# clock-kit-board-002.net
KiCad netlist of a schematic drawn in EAGLE
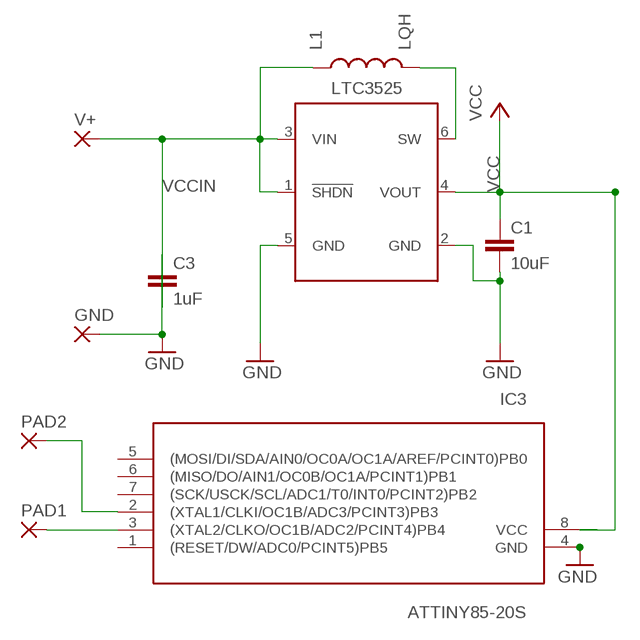
[diagram p0: schematic, sheet 1]

(export (version "E")
  (design (tool "Eeschema 10.0.6"))
  (components
    (comp (ref "C1")
      (value "10uF")
      (footprint "eagle-import:0805")
      (libsource (lib "eagle-import") (part "CAP0805"))
    )
    (comp (ref "C3")
      (value "1uF")
      (footprint "eagle-import:0805")
      (libsource (lib "eagle-import") (part "CAP0805"))
    )
    (comp (ref "GND")
      (value "SMD5")
      (footprint "eagle-import:SMD2,54-5,08")
      (libsource (lib "eagle-import") (part "SMD5"))
    )
    (comp (ref "IC3")
      (value "ATTINY85-20S")
      (footprint "eagle-import:SOIC8")
      (libsource (lib "eagle-import") (part "ATTINY85SV-10"))
    )
    (comp (ref "L1")
      (value "LQH")
      (footprint "eagle-import:LQH32")
      (libsource (lib "eagle-import") (part "LQH"))
    )
    (comp (ref "PAD1")
      (value "1,6/0,9")
      (footprint "eagle-import:1,6_0,9")
      (libsource (lib "eagle-import") (part "1,6/0,9"))
    )
    (comp (ref "PAD2")
      (value "1,6/0,9")
      (footprint "eagle-import:1,6_0,9")
      (libsource (lib "eagle-import") (part "1,6/0,9"))
    )
    (comp (ref "U1")
      (value "LTC3525")
      (footprint "eagle-import:SC70-6L")
      (libsource (lib "eagle-import") (part "LTC3525"))
    )
    (comp (ref "V+")
      (value "SMD5")
      (footprint "eagle-import:SMD2,54-5,08")
      (libsource (lib "eagle-import") (part "SMD5"))
    )
  )
  (nets
    (net (code "1") (name "/VCCIN") (class "Default")
      (node (ref "C3") (pin "2") (pinfunction "2_2") (pintype "passive"))
      (node (ref "L1") (pin "1") (pinfunction "1_1") (pintype "passive"))
      (node (ref "U1") (pin "1") (pinfunction "~{SHDN}_1") (pintype "passive"))
      (node (ref "U1") (pin "3") (pinfunction "VIN_3") (pintype "input"))
      (node (ref "V+") (pin "1") (pinfunction "P_1") (pintype "passive"))
    )
    (net (code "2") (name "GND") (class "Default")
      (node (ref "C1") (pin "2") (pinfunction "2_2") (pintype "passive"))
      (node (ref "C3") (pin "1") (pinfunction "1_1") (pintype "passive"))
      (node (ref "GND") (pin "1") (pinfunction "P_1") (pintype "passive"))
      (node (ref "IC3") (pin "4") (pinfunction "GND_4") (pintype "bidirectional"))
      (node (ref "U1") (pin "2") (pinfunction "GND_2") (pintype "power_in"))
      (node (ref "U1") (pin "5") (pinfunction "GND_5") (pintype "input"))
    )
    (net (code "3") (name "Net-(IC3-(XTAL1{slash}CLKI{slash}OC1B{slash}ADC3{slash}PCINT3)PB3)") (class "Default")
      (node (ref "IC3") (pin "2") (pinfunction "(XTAL1/CLKI/OC1B/ADC3/PCINT3)PB3_2") (pintype "bidirectional"))
      (node (ref "PAD2") (pin "1") (pinfunction "P_1") (pintype "passive"))
    )
    (net (code "4") (name "Net-(IC3-(XTAL2{slash}CLKO{slash}OC1B{slash}ADC2{slash}PCINT4)PB4)") (class "Default")
      (node (ref "IC3") (pin "3") (pinfunction "(XTAL2/CLKO/OC1B/ADC2/PCINT4)PB4_3") (pintype "bidirectional"))
      (node (ref "PAD1") (pin "1") (pinfunction "P_1") (pintype "passive"))
    )
    (net (code "5") (name "Net-(U1-SW)") (class "Default")
      (node (ref "L1") (pin "2") (pinfunction "2_2") (pintype "passive"))
      (node (ref "U1") (pin "6") (pinfunction "SW_6") (pintype "passive"))
    )
    (net (code "6") (name "VCC") (class "Default")
      (node (ref "C1") (pin "1") (pinfunction "1_1") (pintype "passive"))
      (node (ref "IC3") (pin "8") (pinfunction "VCC_8") (pintype "bidirectional"))
      (node (ref "U1") (pin "4") (pinfunction "VOUT_4") (pintype "passive"))
    )
    (net (code "7") (name "unconnected-(IC3-(MISO{slash}DO{slash}AIN1{slash}OC0B{slash}OC1A{slash}PCINT1)PB1-Pad6)") (class "Default")
      (node (ref "IC3") (pin "6") (pinfunction "(MISO/DO/AIN1/OC0B/OC1A/PCINT1)PB1_6") (pintype "bidirectional"))
    )
    (net (code "8") (name "unconnected-(IC3-(MOSI{slash}DI{slash}SDA{slash}AIN0{slash}OC0A{slash}OC1A{slash}AREF{slash}PCINT0)PB0-Pad5)") (class "Default")
      (node (ref "IC3") (pin "5") (pinfunction "(MOSI/DI/SDA/AIN0/OC0A/OC1A/AREF/PCINT0)PB0_5") (pintype "bidirectional"))
    )
    (net (code "9") (name "unconnected-(IC3-(RESET{slash}DW{slash}ADC0{slash}PCINT5)PB5-Pad1)") (class "Default")
      (node (ref "IC3") (pin "1") (pinfunction "(RESET/DW/ADC0/PCINT5)PB5_1") (pintype "bidirectional"))
    )
    (net (code "10") (name "unconnected-(IC3-(SCK{slash}USCK{slash}SCL{slash}ADC1{slash}T0{slash}INT0{slash}PCINT2)PB2-Pad7)") (class "Default")
      (node (ref "IC3") (pin "7") (pinfunction "(SCK/USCK/SCL/ADC1/T0/INT0/PCINT2)PB2_7") (pintype "bidirectional"))
    )
  )
)
